# power.net
KiCad netlist of a schematic drawn in Altium Designer
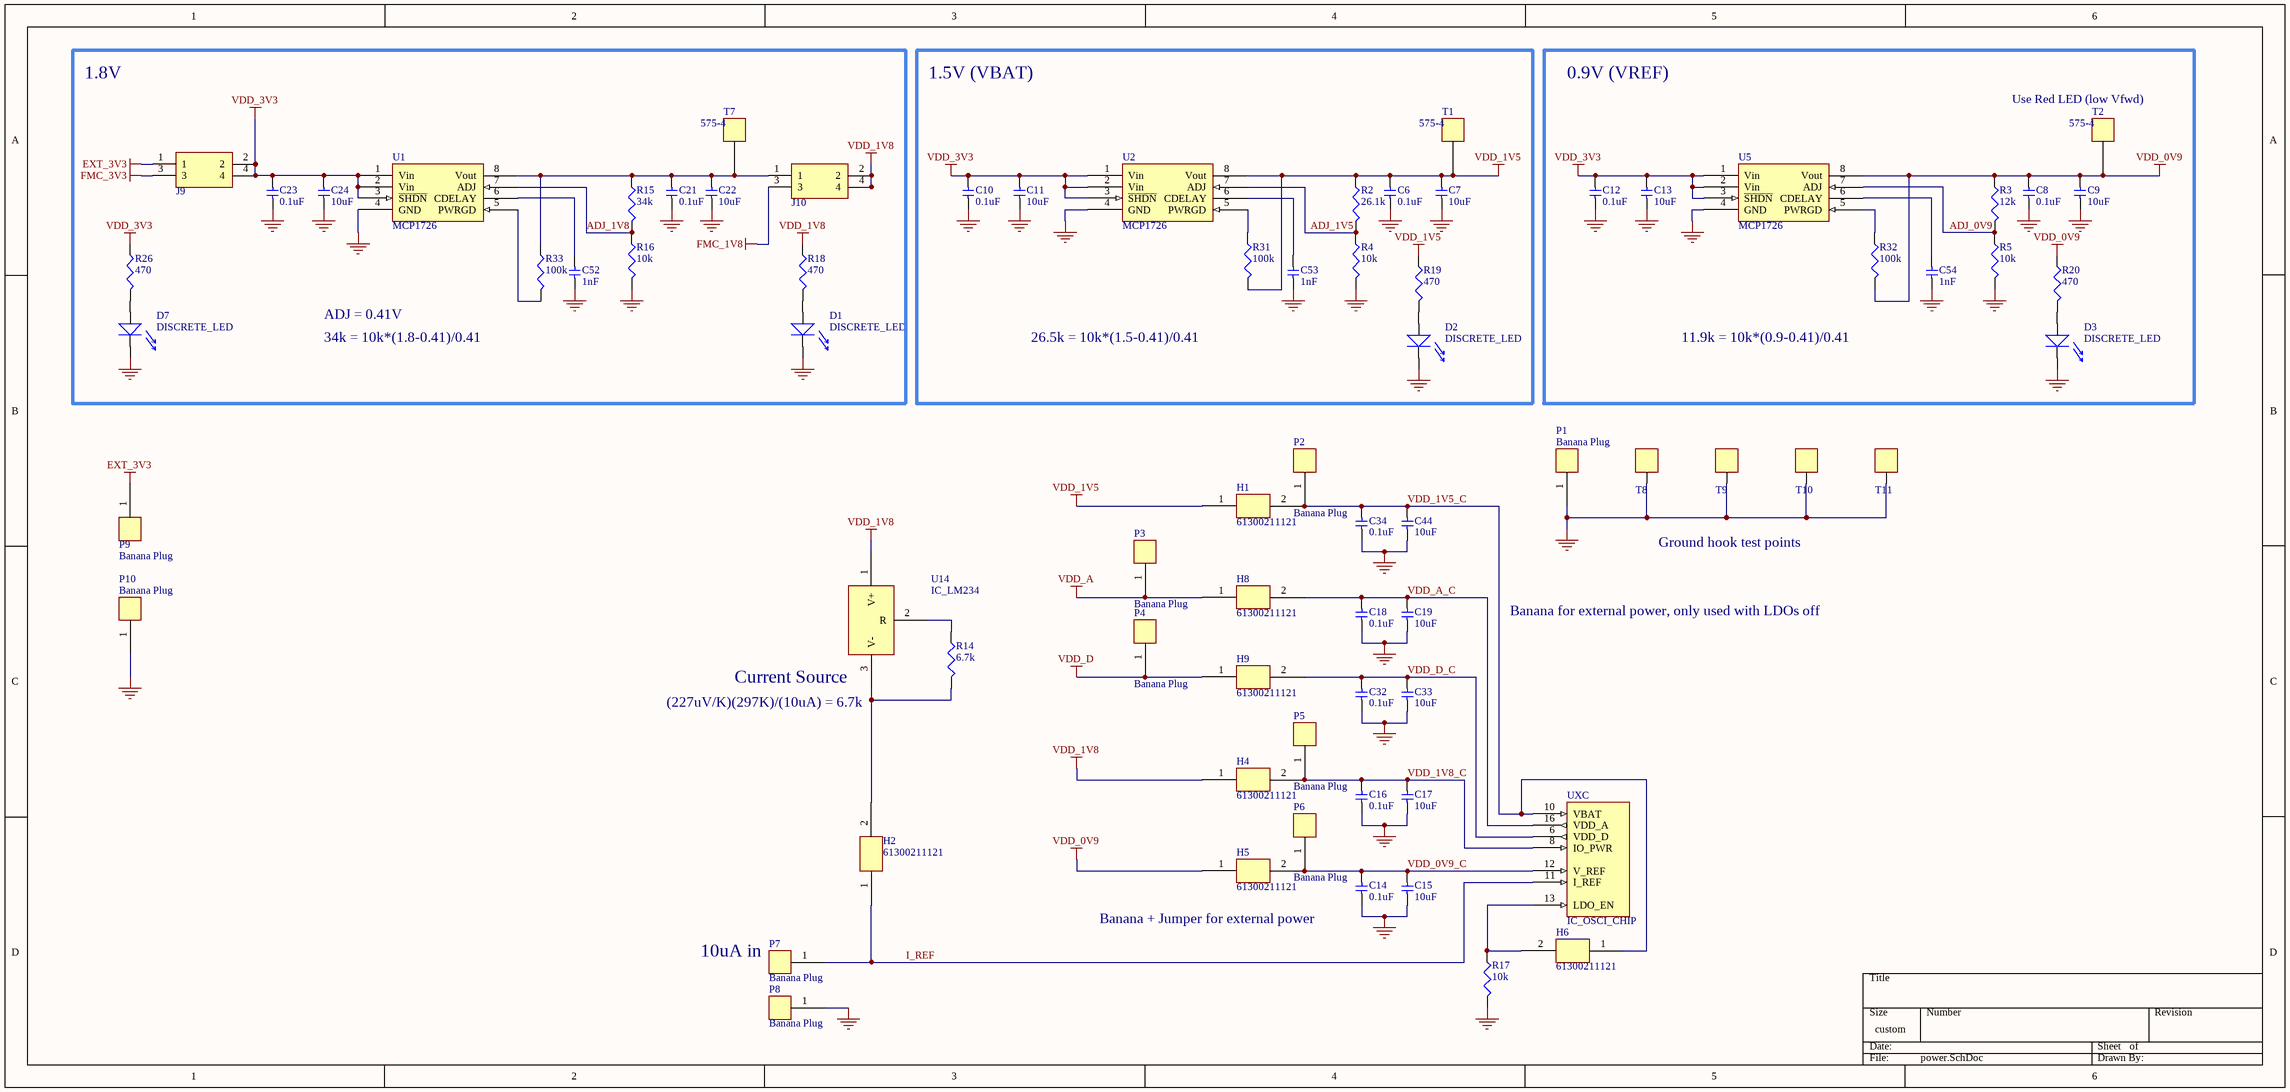
[diagram p0: power.SchDoc]

(export (version "E")
  (design (tool "Eeschema 10.0.6"))
  (components
    (comp (ref "C6")
      (value "0.1uF")
      (footprint "BWRC:0603")
      (description "0.1uF 0402")
      (libsource (lib "BWRC") (part "DISCRETE_C"))
    )
    (comp (ref "C7")
      (value "10uF")
      (footprint "BWRC:0603")
      (description "10uF 0603")
      (libsource (lib "BWRC") (part "DISCRETE_C"))
    )
    (comp (ref "C8")
      (value "0.1uF")
      (footprint "BWRC:0603")
      (description "0.1uF 0402")
      (libsource (lib "BWRC") (part "DISCRETE_C"))
    )
    (comp (ref "C9")
      (value "10uF")
      (footprint "BWRC:0603")
      (description "10uF 0603")
      (libsource (lib "BWRC") (part "DISCRETE_C"))
    )
    (comp (ref "C10")
      (value "0.1uF")
      (footprint "BWRC:0603")
      (description "0.1uF 0402")
      (libsource (lib "BWRC") (part "DISCRETE_C"))
    )
    (comp (ref "C11")
      (value "10uF")
      (footprint "BWRC:0603")
      (description "10uF 0603")
      (libsource (lib "BWRC") (part "DISCRETE_C"))
    )
    (comp (ref "C12")
      (value "0.1uF")
      (footprint "BWRC:0603")
      (description "0.1uF 0402")
      (libsource (lib "BWRC") (part "DISCRETE_C"))
    )
    (comp (ref "C13")
      (value "10uF")
      (footprint "BWRC:0603")
      (description "10uF 0603")
      (libsource (lib "BWRC") (part "DISCRETE_C"))
    )
    (comp (ref "C14")
      (value "0.1uF")
      (footprint "BWRC:0603")
      (description "0.1uF 0402")
      (libsource (lib "BWRC") (part "DISCRETE_C"))
    )
    (comp (ref "C15")
      (value "10uF")
      (footprint "BWRC:0603")
      (description "10uF 0603")
      (libsource (lib "BWRC") (part "DISCRETE_C"))
    )
    (comp (ref "C16")
      (value "0.1uF")
      (footprint "BWRC:0603")
      (description "0.1uF 0402")
      (libsource (lib "BWRC") (part "DISCRETE_C"))
    )
    (comp (ref "C17")
      (value "10uF")
      (footprint "BWRC:0603")
      (description "10uF 0603")
      (libsource (lib "BWRC") (part "DISCRETE_C"))
    )
    (comp (ref "C18")
      (value "0.1uF")
      (footprint "BWRC:0603")
      (description "0.1uF 0402")
      (libsource (lib "BWRC") (part "DISCRETE_C"))
    )
    (comp (ref "C19")
      (value "10uF")
      (footprint "BWRC:0603")
      (description "10uF 0603")
      (libsource (lib "BWRC") (part "DISCRETE_C"))
    )
    (comp (ref "C21")
      (value "0.1uF")
      (footprint "BWRC:0603")
      (description "0.1uF 0402")
      (libsource (lib "BWRC") (part "DISCRETE_C"))
    )
    (comp (ref "C22")
      (value "10uF")
      (footprint "BWRC:0603")
      (description "10uF 0603")
      (libsource (lib "BWRC") (part "DISCRETE_C"))
    )
    (comp (ref "C23")
      (value "0.1uF")
      (footprint "BWRC:0603")
      (description "0.1uF 0402")
      (libsource (lib "BWRC") (part "DISCRETE_C"))
    )
    (comp (ref "C24")
      (value "10uF")
      (footprint "BWRC:0603")
      (description "10uF 0603")
      (libsource (lib "BWRC") (part "DISCRETE_C"))
    )
    (comp (ref "C32")
      (value "0.1uF")
      (footprint "BWRC:0603")
      (description "0.1uF 0402")
      (libsource (lib "BWRC") (part "DISCRETE_C"))
    )
    (comp (ref "C33")
      (value "10uF")
      (footprint "BWRC:0603")
      (description "10uF 0603")
      (libsource (lib "BWRC") (part "DISCRETE_C"))
    )
    (comp (ref "C34")
      (value "0.1uF")
      (footprint "BWRC:0603")
      (description "0.1uF 0402")
      (libsource (lib "BWRC") (part "DISCRETE_C"))
    )
    (comp (ref "C44")
      (value "10uF")
      (footprint "BWRC:0603")
      (description "10uF 0603")
      (libsource (lib "BWRC") (part "DISCRETE_C"))
    )
    (comp (ref "C52")
      (value "1nF")
      (footprint "BWRC:0603")
      (description "0.1uF 0402")
      (libsource (lib "BWRC") (part "DISCRETE_C"))
    )
    (comp (ref "C53")
      (value "1nF")
      (footprint "BWRC:0603")
      (description "0.1uF 0402")
      (libsource (lib "BWRC") (part "DISCRETE_C"))
    )
    (comp (ref "C54")
      (value "1nF")
      (footprint "BWRC:0603")
      (description "0.1uF 0402")
      (libsource (lib "BWRC") (part "DISCRETE_C"))
    )
    (comp (ref "D1")
      (value "DISCRETE_LED")
      (footprint "BWRC:LED-1206")
      (description "LED generic")
      (libsource (lib "BWRC") (part "DISCRETE_LED"))
    )
    (comp (ref "D2")
      (value "DISCRETE_LED")
      (footprint "BWRC:LED-1206")
      (description "LED generic")
      (libsource (lib "BWRC") (part "DISCRETE_LED"))
    )
    (comp (ref "D3")
      (value "DISCRETE_LED")
      (footprint "BWRC:LED-1206")
      (description "LED generic")
      (libsource (lib "BWRC") (part "DISCRETE_LED"))
    )
    (comp (ref "D7")
      (value "DISCRETE_LED")
      (footprint "BWRC:LED-1206")
      (description "LED generic")
      (libsource (lib "BWRC") (part "DISCRETE_LED"))
    )
    (comp (ref "H1")
      (value "61300211121")
      (footprint "CON-002-100-200X100/1X2-POST")
      (libsource (lib "schematic") (part "61300211121"))
    )
    (comp (ref "H2")
      (value "61300211121")
      (footprint "CON-002-100-200X100/1X2-POST")
      (libsource (lib "") (part "61300211121_2"))
    )
    (comp (ref "H4")
      (value "61300211121")
      (footprint "CON-002-100-200X100/1X2-POST")
      (libsource (lib "schematic") (part "61300211121"))
    )
    (comp (ref "H5")
      (value "61300211121")
      (footprint "CON-002-100-200X100/1X2-POST")
      (libsource (lib "schematic") (part "61300211121"))
    )
    (comp (ref "H6")
      (value "61300211121")
      (footprint "CON-002-100-200X100/1X2-POST")
      (libsource (lib "") (part "61300211121_1"))
    )
    (comp (ref "H8")
      (value "61300211121")
      (footprint "CON-002-100-200X100/1X2-POST")
      (libsource (lib "schematic") (part "61300211121"))
    )
    (comp (ref "H9")
      (value "61300211121")
      (footprint "CON-002-100-200X100/1X2-POST")
      (libsource (lib "schematic") (part "61300211121"))
    )
    (comp (ref "J9")
      (value "Con 4 pins 2x2")
      (footprint "CON-004-100-200X200/2X2-POST")
      (libsource (lib "BWRC") (part "CON_004pin_2x2"))
    )
    (comp (ref "J10")
      (value "Con 4 pins 2x2")
      (footprint "CON-004-100-200X200/2X2-POST")
      (libsource (lib "BWRC") (part "CON_004pin_2x2"))
    )
    (comp (ref "P1")
      (value "Banana Plug")
      (footprint "CON-001-312X312/BANANA-JACK")
      (libsource (lib "") (part "Banana Plug_2"))
    )
    (comp (ref "P2")
      (value "Banana Plug")
      (footprint "CON-001-312X312/BANANA-JACK")
      (libsource (lib "") (part "Banana Plug_2"))
    )
    (comp (ref "P3")
      (value "Banana Plug")
      (footprint "CON-001-312X312/BANANA-JACK")
      (libsource (lib "") (part "Banana Plug_2"))
    )
    (comp (ref "P4")
      (value "Banana Plug")
      (footprint "CON-001-312X312/BANANA-JACK")
      (libsource (lib "") (part "Banana Plug_2"))
    )
    (comp (ref "P5")
      (value "Banana Plug")
      (footprint "CON-001-312X312/BANANA-JACK")
      (libsource (lib "") (part "Banana Plug_2"))
    )
    (comp (ref "P6")
      (value "Banana Plug")
      (footprint "CON-001-312X312/BANANA-JACK")
      (libsource (lib "") (part "Banana Plug_2"))
    )
    (comp (ref "P7")
      (value "Banana Plug")
      (footprint "CON-001-312X312/BANANA-JACK")
      (libsource (lib "schematic") (part "Banana Plug"))
    )
    (comp (ref "P8")
      (value "Banana Plug")
      (footprint "CON-001-312X312/BANANA-JACK")
      (libsource (lib "schematic") (part "Banana Plug"))
    )
    (comp (ref "P9")
      (value "Banana Plug")
      (footprint "CON-001-312X312/BANANA-JACK")
      (libsource (lib "") (part "Banana Plug_1"))
    )
    (comp (ref "P10")
      (value "Banana Plug")
      (footprint "CON-001-312X312/BANANA-JACK")
      (libsource (lib "") (part "Banana Plug_2"))
    )
    (comp (ref "R2")
      (value "26.1k")
      (footprint "BWRC:0603")
      (description "200 0402")
      (libsource (lib "BWRC") (part "DISCRETE_R"))
    )
    (comp (ref "R3")
      (value "12k")
      (footprint "BWRC:0603")
      (description "200 0402")
      (libsource (lib "BWRC") (part "DISCRETE_R"))
    )
    (comp (ref "R4")
      (value "10k")
      (footprint "BWRC:0603")
      (description "200 0402")
      (libsource (lib "BWRC") (part "DISCRETE_R"))
    )
    (comp (ref "R5")
      (value "10k")
      (footprint "BWRC:0603")
      (description "200 0402")
      (libsource (lib "BWRC") (part "DISCRETE_R"))
    )
    (comp (ref "R14")
      (value "6.7k")
      (footprint "BWRC:0603")
      (description "Resistor generic")
      (libsource (lib "BWRC") (part "DISCRETE_R"))
    )
    (comp (ref "R15")
      (value "34k")
      (footprint "BWRC:0603")
      (description "200 0402")
      (libsource (lib "BWRC") (part "DISCRETE_R"))
    )
    (comp (ref "R16")
      (value "10k")
      (footprint "BWRC:0603")
      (description "200 0402")
      (libsource (lib "BWRC") (part "DISCRETE_R"))
    )
    (comp (ref "R17")
      (value "10k")
      (footprint "BWRC:0603")
      (description "Resistor generic")
      (libsource (lib "BWRC") (part "DISCRETE_R"))
    )
    (comp (ref "R18")
      (value "470")
      (footprint "BWRC:0603")
      (description "200 0402")
      (libsource (lib "BWRC") (part "DISCRETE_R"))
    )
    (comp (ref "R19")
      (value "470")
      (footprint "BWRC:0603")
      (description "200 0402")
      (libsource (lib "BWRC") (part "DISCRETE_R"))
    )
    (comp (ref "R20")
      (value "470")
      (footprint "BWRC:0603")
      (description "200 0402")
      (libsource (lib "BWRC") (part "DISCRETE_R"))
    )
    (comp (ref "R26")
      (value "470")
      (footprint "BWRC:0603")
      (description "200 0402")
      (libsource (lib "BWRC") (part "DISCRETE_R"))
    )
    (comp (ref "R31")
      (value "100k")
      (footprint "BWRC:0603")
      (description "200 0402")
      (libsource (lib "BWRC") (part "DISCRETE_R"))
    )
    (comp (ref "R32")
      (value "100k")
      (footprint "BWRC:0603")
      (description "200 0402")
      (libsource (lib "BWRC") (part "DISCRETE_R"))
    )
    (comp (ref "R33")
      (value "100k")
      (footprint "BWRC:0603")
      (description "200 0402")
      (libsource (lib "BWRC") (part "DISCRETE_R"))
    )
    (comp (ref "T1")
      (value "575-4")
      (footprint "BWRC:TP-100X100/ROUND-THT")
      (description "Test point")
      (libsource (lib "") (part "TEST_PT_1"))
    )
    (comp (ref "T2")
      (value "575-4")
      (footprint "BWRC:TP-100X100/ROUND-THT")
      (description "Test point")
      (libsource (lib "") (part "TEST_PT_1"))
    )
    (comp (ref "T7")
      (value "575-4")
      (footprint "BWRC:TP-100X100/ROUND-THT")
      (description "Test point")
      (libsource (lib "") (part "TEST_PT_1"))
    )
    (comp (ref "T8")
      (value "Test point 1 pin")
      (footprint "BWRC:TP-100X100/ROUND-THT")
      (libsource (lib "BWRC") (part "TEST_PT"))
    )
    (comp (ref "T9")
      (value "Test point 1 pin")
      (footprint "BWRC:TP-100X100/ROUND-THT")
      (libsource (lib "BWRC") (part "TEST_PT"))
    )
    (comp (ref "T10")
      (value "Test point 1 pin")
      (footprint "BWRC:TP-100X100/ROUND-THT")
      (libsource (lib "BWRC") (part "TEST_PT"))
    )
    (comp (ref "T11")
      (value "Test point 1 pin")
      (footprint "BWRC:TP-100X100/ROUND-THT")
      (libsource (lib "BWRC") (part "TEST_PT"))
    )
    (comp (ref "U1")
      (value "MCP1726")
      (footprint "SOIC-8")
      (description "1A, Low-Voltage, Low Quiescent Current LDO Regulator")
      (libsource (lib "schematic") (part "MCP1726"))
    )
    (comp (ref "U2")
      (value "MCP1726")
      (footprint "SOIC-8")
      (description "1A, Low-Voltage, Low Quiescent Current LDO Regulator")
      (libsource (lib "schematic") (part "MCP1726"))
    )
    (comp (ref "U5")
      (value "MCP1726")
      (footprint "SOIC-8")
      (description "1A, Low-Voltage, Low Quiescent Current LDO Regulator")
      (libsource (lib "schematic") (part "MCP1726"))
    )
    (comp (ref "U14")
      (value "IC_LM234")
      (footprint "TO-92")
      (description "3-Terminal Adjustable Current Sources")
      (libsource (lib "schematic") (part "IC_LM234"))
    )
    (comp (ref "UX")
      (value "IC_OSCI_CHIP")
      (footprint "QFN-48-.4-6.0X6.0-LP")
      (description "EE290C Tapeout Class IC")
      (libsource (lib "schematic") (part "IC_OSCI_CHIP"))
    )
  )
  (nets
    (net (code "1") (name "/ADJ_0V9") (class "Default")
      (node (ref "R3") (pin "2") (pinfunction "2_2") (pintype "passive"))
      (node (ref "R5") (pin "1") (pinfunction "1_1") (pintype "passive"))
      (node (ref "U5") (pin "7") (pinfunction "ADJ_7") (pintype "input"))
    )
    (net (code "2") (name "/ADJ_1V5") (class "Default")
      (node (ref "R2") (pin "2") (pinfunction "2_2") (pintype "passive"))
      (node (ref "R4") (pin "1") (pinfunction "1_1") (pintype "passive"))
      (node (ref "U2") (pin "7") (pinfunction "ADJ_7") (pintype "input"))
    )
    (net (code "3") (name "/ADJ_1V8") (class "Default")
      (node (ref "R15") (pin "2") (pinfunction "2_2") (pintype "passive"))
      (node (ref "R16") (pin "1") (pinfunction "1_1") (pintype "passive"))
      (node (ref "U1") (pin "7") (pinfunction "ADJ_7") (pintype "input"))
    )
    (net (code "4") (name "/I_REF") (class "Default")
      (node (ref "H2") (pin "1") (pintype "power_in"))
      (node (ref "P7") (pin "1") (pintype "passive"))
      (node (ref "UX") (pin "11") (pinfunction "I_REF_11") (pintype "input"))
    )
    (net (code "5") (name "/VDD_0V9_C") (class "Default")
      (node (ref "C14") (pin "1") (pinfunction "1_1") (pintype "passive"))
      (node (ref "C15") (pin "1") (pinfunction "1_1") (pintype "passive"))
      (node (ref "H5") (pin "2") (pintype "passive"))
      (node (ref "P6") (pin "1") (pintype "passive"))
      (node (ref "UX") (pin "12") (pinfunction "V_REF_12") (pintype "input"))
    )
    (net (code "6") (name "/VDD_1V5_C") (class "Default")
      (node (ref "C34") (pin "1") (pinfunction "1_1") (pintype "passive"))
      (node (ref "C44") (pin "1") (pinfunction "1_1") (pintype "passive"))
      (node (ref "H1") (pin "2") (pintype "passive"))
      (node (ref "H6") (pin "1") (pintype "power_in"))
      (node (ref "P2") (pin "1") (pintype "passive"))
      (node (ref "UX") (pin "10") (pinfunction "VBAT_10") (pintype "input"))
    )
    (net (code "7") (name "/VDD_1V8_C") (class "Default")
      (node (ref "C16") (pin "1") (pinfunction "1_1") (pintype "passive"))
      (node (ref "C17") (pin "1") (pinfunction "1_1") (pintype "passive"))
      (node (ref "H4") (pin "2") (pintype "passive"))
      (node (ref "P5") (pin "1") (pintype "passive"))
      (node (ref "UX") (pin "8") (pinfunction "IO_PWR_8") (pintype "input"))
    )
    (net (code "8") (name "/VDD_A_C") (class "Default")
      (node (ref "C18") (pin "1") (pinfunction "1_1") (pintype "passive"))
      (node (ref "C19") (pin "1") (pinfunction "1_1") (pintype "passive"))
      (node (ref "H8") (pin "2") (pintype "passive"))
      (node (ref "UX") (pin "16") (pinfunction "VDD_A_16") (pintype "output"))
    )
    (net (code "9") (name "/VDD_D_C") (class "Default")
      (node (ref "C32") (pin "1") (pinfunction "1_1") (pintype "passive"))
      (node (ref "C33") (pin "1") (pinfunction "1_1") (pintype "passive"))
      (node (ref "H9") (pin "2") (pintype "passive"))
      (node (ref "UX") (pin "6") (pinfunction "VDD_D_6") (pintype "output"))
    )
    (net (code "10") (name "EXT_3V3") (class "Default")
      (node (ref "J9") (pin "1") (pinfunction "1_1") (pintype "passive"))
      (node (ref "P9") (pin "1") (pintype "passive"))
    )
    (net (code "11") (name "FMC_1V8") (class "Default")
      (node (ref "J10") (pin "3") (pinfunction "3_3") (pintype "passive"))
    )
    (net (code "12") (name "FMC_3V3") (class "Default")
      (node (ref "J9") (pin "3") (pinfunction "3_3") (pintype "passive"))
    )
    (net (code "13") (name "GND") (class "Default")
      (node (ref "C10") (pin "2") (pinfunction "2_2") (pintype "passive"))
      (node (ref "C11") (pin "2") (pinfunction "2_2") (pintype "passive"))
      (node (ref "C12") (pin "2") (pinfunction "2_2") (pintype "passive"))
      (node (ref "C13") (pin "2") (pinfunction "2_2") (pintype "passive"))
      (node (ref "C14") (pin "2") (pinfunction "2_2") (pintype "passive"))
      (node (ref "C15") (pin "2") (pinfunction "2_2") (pintype "passive"))
      (node (ref "C16") (pin "2") (pinfunction "2_2") (pintype "passive"))
      (node (ref "C17") (pin "2") (pinfunction "2_2") (pintype "passive"))
      (node (ref "C18") (pin "2") (pinfunction "2_2") (pintype "passive"))
      (node (ref "C19") (pin "2") (pinfunction "2_2") (pintype "passive"))
      (node (ref "C21") (pin "2") (pinfunction "2_2") (pintype "passive"))
      (node (ref "C22") (pin "2") (pinfunction "2_2") (pintype "passive"))
      (node (ref "C23") (pin "2") (pinfunction "2_2") (pintype "passive"))
      (node (ref "C24") (pin "2") (pinfunction "2_2") (pintype "passive"))
      (node (ref "C32") (pin "2") (pinfunction "2_2") (pintype "passive"))
      (node (ref "C33") (pin "2") (pinfunction "2_2") (pintype "passive"))
      (node (ref "C34") (pin "2") (pinfunction "2_2") (pintype "passive"))
      (node (ref "C44") (pin "2") (pinfunction "2_2") (pintype "passive"))
      (node (ref "C52") (pin "2") (pinfunction "2_2") (pintype "passive"))
      (node (ref "C53") (pin "2") (pinfunction "2_2") (pintype "passive"))
      (node (ref "C54") (pin "2") (pinfunction "2_2") (pintype "passive"))
      (node (ref "C6") (pin "2") (pinfunction "2_2") (pintype "passive"))
      (node (ref "C7") (pin "2") (pinfunction "2_2") (pintype "passive"))
      (node (ref "C8") (pin "2") (pinfunction "2_2") (pintype "passive"))
      (node (ref "C9") (pin "2") (pinfunction "2_2") (pintype "passive"))
      (node (ref "D1") (pin "1") (pinfunction "1_1") (pintype "passive"))
      (node (ref "D2") (pin "1") (pinfunction "1_1") (pintype "passive"))
      (node (ref "D3") (pin "1") (pinfunction "1_1") (pintype "passive"))
      (node (ref "D7") (pin "1") (pinfunction "1_1") (pintype "passive"))
      (node (ref "P1") (pin "1") (pintype "passive"))
      (node (ref "P10") (pin "1") (pintype "passive"))
      (node (ref "P8") (pin "1") (pintype "passive"))
      (node (ref "R16") (pin "2") (pinfunction "2_2") (pintype "passive"))
      (node (ref "R17") (pin "2") (pinfunction "2_2") (pintype "passive"))
      (node (ref "R4") (pin "2") (pinfunction "2_2") (pintype "passive"))
      (node (ref "R5") (pin "2") (pinfunction "2_2") (pintype "passive"))
      (node (ref "T10") (pin "1") (pinfunction "1_1") (pintype "passive"))
      (node (ref "T11") (pin "1") (pinfunction "1_1") (pintype "passive"))
      (node (ref "T8") (pin "1") (pinfunction "1_1") (pintype "passive"))
      (node (ref "T9") (pin "1") (pinfunction "1_1") (pintype "passive"))
      (node (ref "U1") (pin "4") (pinfunction "GND_4") (pintype "power_in"))
      (node (ref "U2") (pin "4") (pinfunction "GND_4") (pintype "power_in"))
      (node (ref "U5") (pin "4") (pinfunction "GND_4") (pintype "power_in"))
    )
    (net (code "14") (name "Net-(D1-Pad2)") (class "Default")
      (node (ref "D1") (pin "2") (pinfunction "2_2") (pintype "passive"))
      (node (ref "R18") (pin "2") (pinfunction "2_2") (pintype "passive"))
    )
    (net (code "15") (name "Net-(D2-Pad2)") (class "Default")
      (node (ref "D2") (pin "2") (pinfunction "2_2") (pintype "passive"))
      (node (ref "R19") (pin "2") (pinfunction "2_2") (pintype "passive"))
    )
    (net (code "16") (name "Net-(D3-Pad2)") (class "Default")
      (node (ref "D3") (pin "2") (pinfunction "2_2") (pintype "passive"))
      (node (ref "R20") (pin "2") (pinfunction "2_2") (pintype "passive"))
    )
    (net (code "17") (name "Net-(D7-Pad2)") (class "Default")
      (node (ref "D7") (pin "2") (pinfunction "2_2") (pintype "passive"))
      (node (ref "R26") (pin "2") (pinfunction "2_2") (pintype "passive"))
    )
    (net (code "18") (name "Net-(U1-CDELAY)") (class "Default")
      (node (ref "C52") (pin "1") (pinfunction "1_1") (pintype "passive"))
      (node (ref "U1") (pin "6") (pinfunction "CDELAY_6") (pintype "passive"))
    )
    (net (code "19") (name "Net-(U1-PWRGD)") (class "Default")
      (node (ref "R33") (pin "2") (pinfunction "2_2") (pintype "passive"))
      (node (ref "U1") (pin "5") (pinfunction "PWRGD_5") (pintype "input"))
    )
    (net (code "20") (name "Net-(U1-Vout)") (class "Default")
      (node (ref "C21") (pin "1") (pinfunction "1_1") (pintype "passive"))
      (node (ref "C22") (pin "1") (pinfunction "1_1") (pintype "passive"))
      (node (ref "J10") (pin "1") (pinfunction "1_1") (pintype "passive"))
      (node (ref "R15") (pin "1") (pinfunction "1_1") (pintype "passive"))
      (node (ref "R33") (pin "1") (pinfunction "1_1") (pintype "passive"))
      (node (ref "T7") (pin "1") (pinfunction "1_1") (pintype "passive"))
      (node (ref "U1") (pin "8") (pinfunction "Vout_8") (pintype "power_in"))
    )
    (net (code "21") (name "Net-(U2-CDELAY)") (class "Default")
      (node (ref "C53") (pin "1") (pinfunction "1_1") (pintype "passive"))
      (node (ref "U2") (pin "6") (pinfunction "CDELAY_6") (pintype "passive"))
    )
    (net (code "22") (name "Net-(U2-PWRGD)") (class "Default")
      (node (ref "R31") (pin "1") (pinfunction "1_1") (pintype "passive"))
      (node (ref "U2") (pin "5") (pinfunction "PWRGD_5") (pintype "input"))
    )
    (net (code "23") (name "Net-(U5-CDELAY)") (class "Default")
      (node (ref "C54") (pin "1") (pinfunction "1_1") (pintype "passive"))
      (node (ref "U5") (pin "6") (pinfunction "CDELAY_6") (pintype "passive"))
    )
    (net (code "24") (name "Net-(U5-PWRGD)") (class "Default")
      (node (ref "R32") (pin "1") (pinfunction "1_1") (pintype "passive"))
      (node (ref "U5") (pin "5") (pinfunction "PWRGD_5") (pintype "input"))
    )
    (net (code "25") (name "Net-(U14-R)") (class "Default")
      (node (ref "R14") (pin "1") (pinfunction "1_1") (pintype "passive"))
      (node (ref "U14") (pin "2") (pinfunction "R_2") (pintype "passive"))
    )
    (net (code "26") (name "Net-(U14-V-)") (class "Default")
      (node (ref "H2") (pin "2") (pintype "power_in"))
      (node (ref "R14") (pin "2") (pinfunction "2_2") (pintype "passive"))
      (node (ref "U14") (pin "3") (pinfunction "V-_3") (pintype "passive"))
    )
    (net (code "27") (name "Net-(UXC-LDO_EN)") (class "Default")
      (node (ref "H6") (pin "2") (pintype "power_in"))
      (node (ref "R17") (pin "1") (pinfunction "1_1") (pintype "passive"))
      (node (ref "UX") (pin "13") (pinfunction "LDO_EN_13") (pintype "input"))
    )
    (net (code "28") (name "VDD_0V9") (class "Default")
      (node (ref "C8") (pin "1") (pinfunction "1_1") (pintype "passive"))
      (node (ref "C9") (pin "1") (pinfunction "1_1") (pintype "passive"))
      (node (ref "H5") (pin "1") (pintype "passive"))
      (node (ref "R20") (pin "1") (pinfunction "1_1") (pintype "passive"))
      (node (ref "R3") (pin "1") (pinfunction "1_1") (pintype "passive"))
      (node (ref "R32") (pin "2") (pinfunction "2_2") (pintype "passive"))
      (node (ref "T2") (pin "1") (pinfunction "1_1") (pintype "passive"))
      (node (ref "U5") (pin "8") (pinfunction "Vout_8") (pintype "power_in"))
    )
    (net (code "29") (name "VDD_1V5") (class "Default")
      (node (ref "C6") (pin "1") (pinfunction "1_1") (pintype "passive"))
      (node (ref "C7") (pin "1") (pinfunction "1_1") (pintype "passive"))
      (node (ref "H1") (pin "1") (pintype "passive"))
      (node (ref "R19") (pin "1") (pinfunction "1_1") (pintype "passive"))
      (node (ref "R2") (pin "1") (pinfunction "1_1") (pintype "passive"))
      (node (ref "R31") (pin "2") (pinfunction "2_2") (pintype "passive"))
      (node (ref "T1") (pin "1") (pinfunction "1_1") (pintype "passive"))
      (node (ref "U2") (pin "8") (pinfunction "Vout_8") (pintype "power_in"))
    )
    (net (code "30") (name "VDD_1V8") (class "Default")
      (node (ref "H4") (pin "1") (pintype "passive"))
      (node (ref "J10") (pin "2") (pinfunction "2_2") (pintype "passive"))
      (node (ref "J10") (pin "4") (pinfunction "4_4") (pintype "passive"))
      (node (ref "R18") (pin "1") (pinfunction "1_1") (pintype "passive"))
      (node (ref "U14") (pin "1") (pinfunction "V+_1") (pintype "passive"))
    )
    (net (code "31") (name "VDD_3V3") (class "Default")
      (node (ref "C10") (pin "1") (pinfunction "1_1") (pintype "passive"))
      (node (ref "C11") (pin "1") (pinfunction "1_1") (pintype "passive"))
      (node (ref "C12") (pin "1") (pinfunction "1_1") (pintype "passive"))
      (node (ref "C13") (pin "1") (pinfunction "1_1") (pintype "passive"))
      (node (ref "C23") (pin "1") (pinfunction "1_1") (pintype "passive"))
      (node (ref "C24") (pin "1") (pinfunction "1_1") (pintype "passive"))
      (node (ref "J9") (pin "2") (pinfunction "2_2") (pintype "passive"))
      (node (ref "J9") (pin "4") (pinfunction "4_4") (pintype "passive"))
      (node (ref "R26") (pin "1") (pinfunction "1_1") (pintype "passive"))
      (node (ref "U1") (pin "1") (pinfunction "Vin_1") (pintype "power_in"))
      (node (ref "U1") (pin "2") (pinfunction "Vin_2") (pintype "power_in"))
      (node (ref "U1") (pin "3") (pinfunction "~{SHDN}_3") (pintype "input"))
      (node (ref "U2") (pin "1") (pinfunction "Vin_1") (pintype "power_in"))
      (node (ref "U2") (pin "2") (pinfunction "Vin_2") (pintype "power_in"))
      (node (ref "U2") (pin "3") (pinfunction "~{SHDN}_3") (pintype "input"))
      (node (ref "U5") (pin "1") (pinfunction "Vin_1") (pintype "power_in"))
      (node (ref "U5") (pin "2") (pinfunction "Vin_2") (pintype "power_in"))
      (node (ref "U5") (pin "3") (pinfunction "~{SHDN}_3") (pintype "input"))
    )
    (net (code "32") (name "VDD_A") (class "Default")
      (node (ref "H8") (pin "1") (pintype "passive"))
      (node (ref "P3") (pin "1") (pintype "passive"))
    )
    (net (code "33") (name "VDD_D") (class "Default")
      (node (ref "H9") (pin "1") (pintype "passive"))
      (node (ref "P4") (pin "1") (pintype "passive"))
    )
  )
)
